# power.net
KiCad netlist of a schematic drawn in Altium Designer
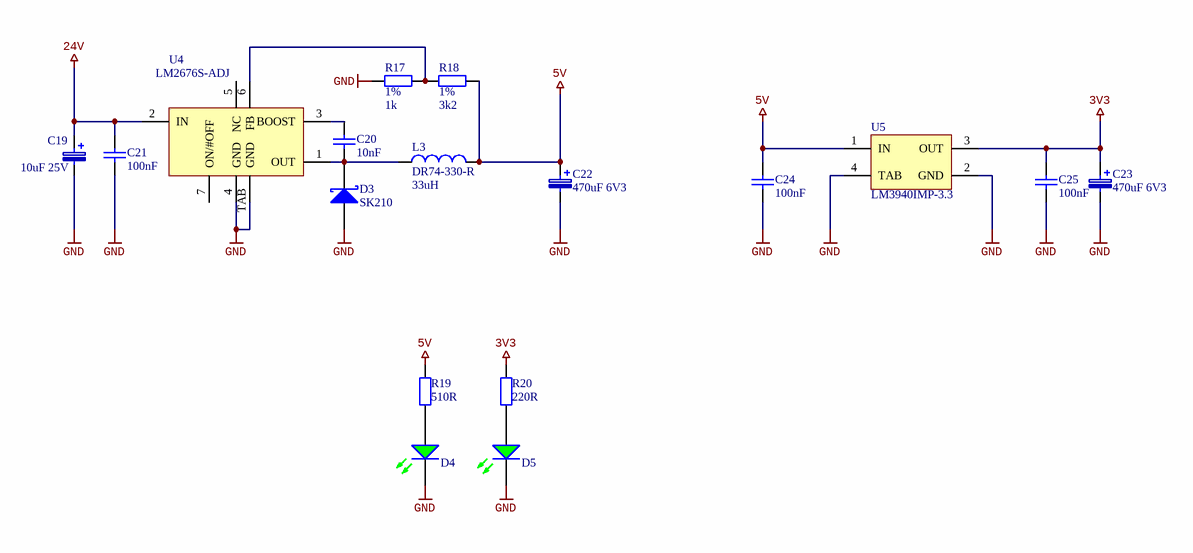
[diagram p0: power.SchDoc]

(export (version "E")
  (design (tool "Eeschema 10.0.6"))
  (components
    (comp (ref "C19")
      (value "10uF 25V")
      (footprint "SMDB")
      (description "Capacitor Tantalum")
      (libsource (lib "Discrete") (part "Capacitor Tantalum"))
    )
    (comp (ref "C20")
      (value "10nF")
      (footprint "CAPC1608N")
      (description "Capacitor")
      (libsource (lib "Discrete") (part "Capacitor"))
    )
    (comp (ref "C21")
      (value "100nF")
      (footprint "CAPC1608N")
      (description "Capacitor")
      (libsource (lib "Discrete") (part "Capacitor"))
    )
    (comp (ref "C22")
      (value "470uF 6V3")
      (footprint "Mechatronic:SMDD")
      (description "Polarized Capacitor (Surface Mount)")
      (libsource (lib "Mechatronic") (part "10uF 35V-SMDD"))
    )
    (comp (ref "C23")
      (value "470uF 6V3")
      (footprint "Mechatronic:SMDD")
      (description "Polarized Capacitor (Surface Mount)")
      (libsource (lib "Mechatronic") (part "10uF 35V-SMDD"))
    )
    (comp (ref "C24")
      (value "100nF")
      (footprint "CAPC1608N")
      (description "Capacitor")
      (fields (field (name "PUBLISHER") "Altium Limited"))
      (libsource (lib "Miscellaneous Devices") (part "Cap"))
    )
    (comp (ref "C25")
      (value "100nF")
      (footprint "CAPC1608N")
      (description "Capacitor")
      (fields (field (name "PUBLISHER") "Altium Limited"))
      (libsource (lib "Miscellaneous Devices") (part "Cap"))
    )
    (comp (ref "D3")
      (value "SK210")
      (footprint "Mechatronic:SMB")
      (description "Schottky Barrier Rectifier,  40V, 3A")
      (libsource (lib "Mechatronic") (part "MBRS340T3"))
    )
    (comp (ref "D4")
      (value "LL-S172GC-2A")
      (footprint "Chip Diode - 2 Contacts:CD2012-0805")
      (description "Typical GREEN LED")
      (fields (field (name "MANUFACTURER") "Lucky Light"))
      (libsource (lib "Discrete") (part "Led Green"))
    )
    (comp (ref "D5")
      (value "LL-S172GC-2A")
      (footprint "Chip Diode - 2 Contacts:CD2012-0805")
      (description "Typical GREEN LED")
      (fields (field (name "MANUFACTURER") "Lucky Light"))
      (libsource (lib "Discrete") (part "Led Green"))
    )
    (comp (ref "L3")
      (value "DR74-330-R")
      (footprint "Mechatronic:DR74 Series")
      (fields (field (name "ALTIUM_VALUE") "33uH") (field (name "PUBLISHER") "Altium Limited"))
      (libsource (lib "Mechatronic") (part "DR74-330-R"))
    )
    (comp (ref "R17")
      (value "1k")
      (footprint "RESC1608N")
      (description "Resistor")
      (fields (field (name "TOLERANCE") "1%") (field (name "POWER") "0W"))
      (libsource (lib "") (part "Resistor_1"))
    )
    (comp (ref "R18")
      (value "3k2")
      (footprint "RESC1608N")
      (description "Resistor")
      (fields (field (name "TOLERANCE") "1%") (field (name "POWER") "0W"))
      (libsource (lib "") (part "Resistor_1"))
    )
    (comp (ref "R19")
      (value "510R")
      (footprint "RESC1608N")
      (description "Resistor")
      (fields (field (name "TOLERANCE") "5%") (field (name "POWER") "0W"))
      (libsource (lib "Discrete") (part "Resistor"))
    )
    (comp (ref "R20")
      (value "220R")
      (footprint "RESC1608N")
      (description "Resistor")
      (fields (field (name "TOLERANCE") "5%") (field (name "POWER") "0W"))
      (libsource (lib "Discrete") (part "Resistor"))
    )
    (comp (ref "U4")
      (value "LM2676S-ADJ")
      (footprint "TO-263-7")
      (description "SIMPLE SWITCHER High Efficiency 3A Step-Down Voltage Regulator")
      (libsource (lib "Mechatronic") (part "LM2676S-ADJ"))
    )
    (comp (ref "U5")
      (value "LM3940IMP-3.3")
      (footprint "MP04A_N")
      (description "1A Low Dropout Regulator for 5V to 3.3V Conversion, 4-pin SOT-223")
      (fields
        (field (name "MANUFACTURER") "National Semiconductor")
        (field (name "PUBLISHER") "Altium Limited")
      )
      (libsource (lib "NSC LDO") (part "LM3940IMP-3.3"))
    )
  )
  (nets
    (net (code "1") (name "3V3") (class "Default")
      (node (ref "C23") (pin "1") (pinfunction "1_1") (pintype "passive"))
      (node (ref "C25") (pin "2") (pinfunction "2_2") (pintype "passive"))
      (node (ref "R20") (pin "1") (pinfunction "1_1") (pintype "passive"))
      (node (ref "U5") (pin "3") (pinfunction "OUT_3") (pintype "power_in"))
    )
    (net (code "2") (name "5V") (class "Default")
      (node (ref "C22") (pin "1") (pinfunction "1_1") (pintype "passive"))
      (node (ref "C24") (pin "2") (pinfunction "2_2") (pintype "passive"))
      (node (ref "L3") (pin "2") (pinfunction "2_2") (pintype "passive"))
      (node (ref "R18") (pin "2") (pinfunction "2_2") (pintype "passive"))
      (node (ref "R19") (pin "1") (pinfunction "1_1") (pintype "passive"))
      (node (ref "U5") (pin "1") (pinfunction "IN_1") (pintype "power_in"))
    )
    (net (code "3") (name "24V") (class "Default")
      (node (ref "C19") (pin "1") (pinfunction "1_1") (pintype "passive"))
      (node (ref "C21") (pin "2") (pinfunction "2_2") (pintype "passive"))
      (node (ref "U4") (pin "2") (pinfunction "IN_2") (pintype "passive"))
    )
    (net (code "4") (name "GND") (class "Default")
      (node (ref "C19") (pin "2") (pinfunction "2_2") (pintype "passive"))
      (node (ref "C21") (pin "1") (pinfunction "1_1") (pintype "passive"))
      (node (ref "C22") (pin "2") (pinfunction "2_2") (pintype "passive"))
      (node (ref "C23") (pin "2") (pinfunction "2_2") (pintype "passive"))
      (node (ref "C24") (pin "1") (pinfunction "1_1") (pintype "passive"))
      (node (ref "C25") (pin "1") (pinfunction "1_1") (pintype "passive"))
      (node (ref "D3") (pin "1") (pinfunction "A_1") (pintype "passive"))
      (node (ref "D4") (pin "2") (pinfunction "K_2") (pintype "passive"))
      (node (ref "D5") (pin "2") (pinfunction "K_2") (pintype "passive"))
      (node (ref "R17") (pin "1") (pinfunction "1_1") (pintype "passive"))
      (node (ref "U4") (pin "4") (pinfunction "GND_4") (pintype "passive"))
      (node (ref "U4") (pin "TAB") (pinfunction "GND_TAB") (pintype "passive"))
      (node (ref "U5") (pin "2") (pinfunction "GND_2") (pintype "power_in"))
      (node (ref "U5") (pin "4") (pinfunction "TAB_4") (pintype "power_in"))
    )
    (net (code "5") (name "Net-(D3-K)") (class "Default")
      (node (ref "C20") (pin "1") (pinfunction "1_1") (pintype "passive"))
      (node (ref "D3") (pin "2") (pinfunction "K_2") (pintype "passive"))
      (node (ref "L3") (pin "1") (pinfunction "1_1") (pintype "passive"))
      (node (ref "U4") (pin "1") (pinfunction "OUT_1") (pintype "passive"))
    )
    (net (code "6") (name "Net-(D4-A)") (class "Default")
      (node (ref "D4") (pin "1") (pinfunction "A_1") (pintype "passive"))
      (node (ref "R19") (pin "2") (pinfunction "2_2") (pintype "passive"))
    )
    (net (code "7") (name "Net-(D5-A)") (class "Default")
      (node (ref "D5") (pin "1") (pinfunction "A_1") (pintype "passive"))
      (node (ref "R20") (pin "2") (pinfunction "2_2") (pintype "passive"))
    )
    (net (code "8") (name "Net-(U4-BOOST)") (class "Default")
      (node (ref "C20") (pin "2") (pinfunction "2_2") (pintype "passive"))
      (node (ref "U4") (pin "3") (pinfunction "BOOST_3") (pintype "passive"))
    )
    (net (code "9") (name "Net-(U4-FB)") (class "Default")
      (node (ref "R17") (pin "2") (pinfunction "2_2") (pintype "passive"))
      (node (ref "R18") (pin "1") (pinfunction "1_1") (pintype "passive"))
      (node (ref "U4") (pin "6") (pinfunction "FB_6") (pintype "passive"))
    )
    (net (code "10") (name "unconnected-(U4-NC-Pad5)") (class "Default")
      (node (ref "U4") (pin "5") (pinfunction "NC_5") (pintype "passive"))
    )
    (net (code "11") (name "unconnected-(U4-ON{slash}#OFF-Pad7)") (class "Default")
      (node (ref "U4") (pin "7") (pinfunction "ON/#OFF_7") (pintype "passive"))
    )
  )
)
